# SCH_System.net
KiCad netlist of a schematic drawn in Altium Designer
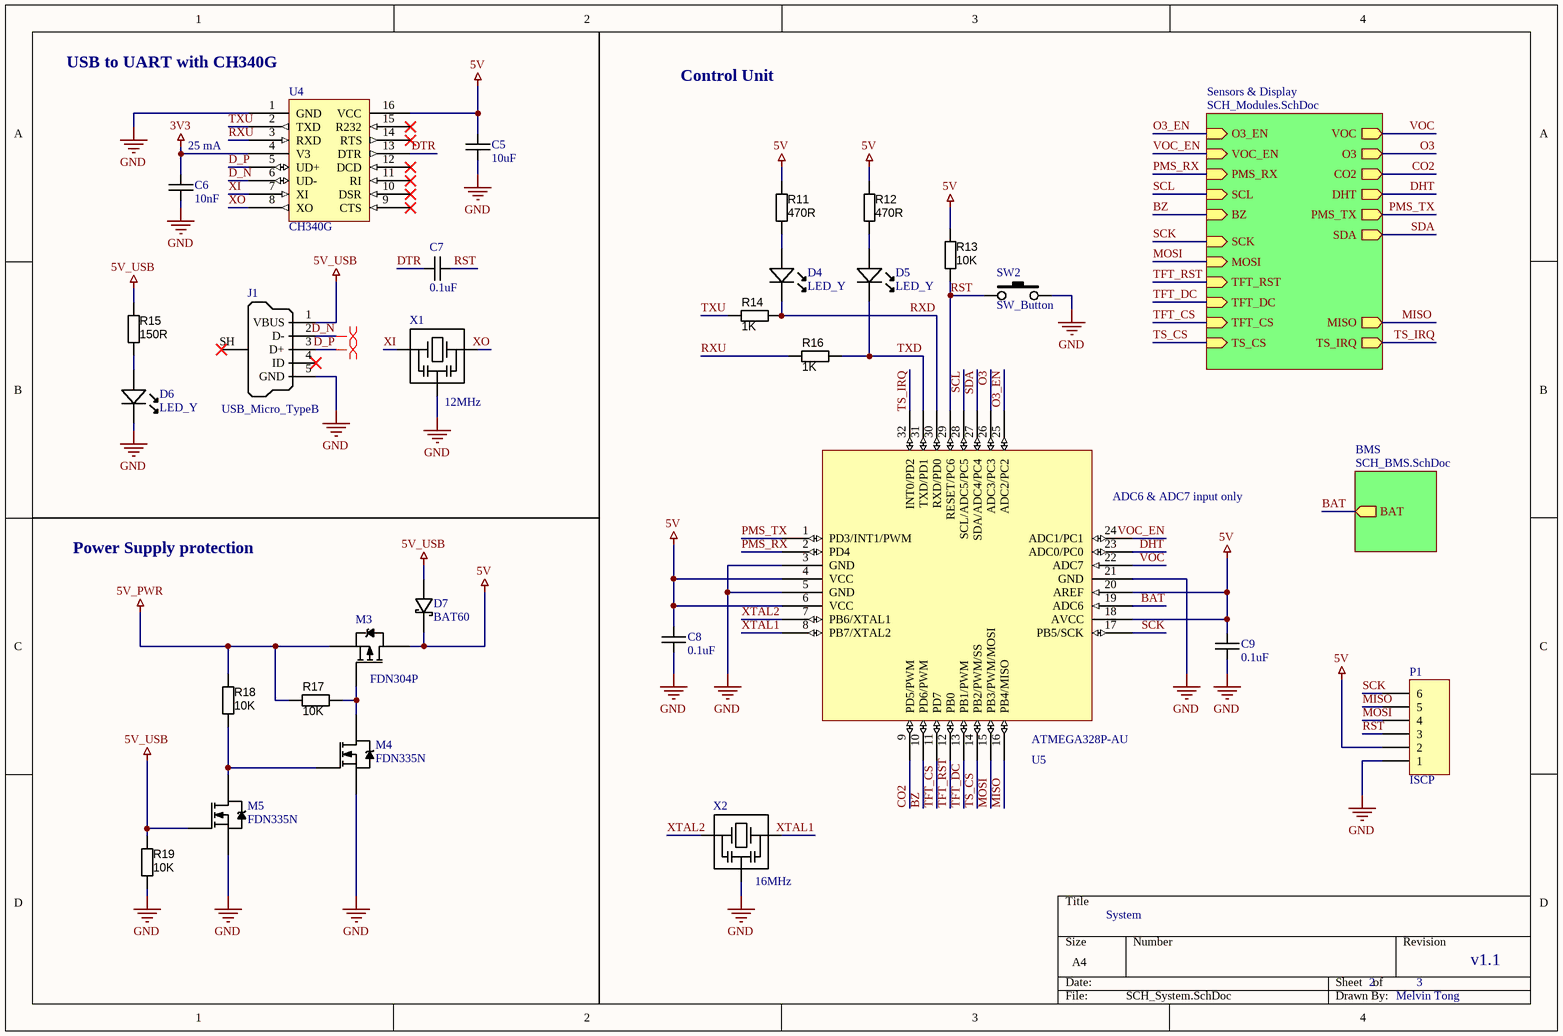
[diagram p0: SCH_System.SchDoc]

(export (version "E")
  (design (tool "Eeschema 10.0.6"))
  (components
    (comp (ref "C5")
      (value "10uF")
      (footprint "CAP_0805")
      (description "SMD 0805")
      (libsource (lib "SchLib_AirMeter") (part "CAP_10uF"))
    )
    (comp (ref "C6")
      (value "10nF")
      (footprint "CAP_0805")
      (description "SMD 0805")
      (libsource (lib "SchLib_AirMeter") (part "CAP_10nF"))
    )
    (comp (ref "C7")
      (value "0.1uF")
      (footprint "CAP_0805")
      (description "SMD 0805")
      (libsource (lib "SchLib_AirMeter") (part "CAP_0.1uF"))
    )
    (comp (ref "C8")
      (value "0.1uF")
      (footprint "CAP_0805")
      (description "SMD 0805")
      (libsource (lib "SchLib_AirMeter") (part "CAP_0.1uF"))
    )
    (comp (ref "C9")
      (value "0.1uF")
      (footprint "CAP_0805")
      (description "SMD 0805")
      (libsource (lib "SchLib_AirMeter") (part "CAP_0.1uF"))
    )
    (comp (ref "D4")
      (value "LED_Y")
      (footprint "LED_0805")
      (description "SMD_0805 2.4V")
      (libsource (lib "SchLib_AirMeter") (part "LED_Y"))
    )
    (comp (ref "D5")
      (value "LED_Y")
      (footprint "LED_0805")
      (description "SMD_0805 2.4V")
      (libsource (lib "SchLib_AirMeter") (part "LED_Y"))
    )
    (comp (ref "D6")
      (value "LED_Y")
      (footprint "LED_0805")
      (description "SMD_0805 2.4V")
      (libsource (lib "SchLib_AirMeter") (part "LED_Y"))
    )
    (comp (ref "D7")
      (value "BAT60")
      (footprint "SOD323")
      (description "Schottky Diode 3A, Vf~0.24V, Vr=10V")
      (libsource (lib "SchLib_AirMeter") (part "BAT60"))
    )
    (comp (ref "J1")
      (value "USB_Micro_TypeB")
      (footprint "USB_Micro_TypeB")
      (libsource (lib "SchLib_AirMeter") (part "USB_Micro_TypeB"))
    )
    (comp (ref "M3")
      (value "FDN304P")
      (footprint "SOT23_213")
      (libsource (lib "SchLib_AirMeter") (part "PMOS"))
    )
    (comp (ref "M4")
      (value "FDN335N")
      (footprint "SOT23_213")
      (libsource (lib "SchLib_AirMeter") (part "NMOS"))
    )
    (comp (ref "M5")
      (value "FDN335N")
      (footprint "SOT23_213")
      (libsource (lib "SchLib_AirMeter") (part "NMOS"))
    )
    (comp (ref "P1")
      (value "ISCP")
      (footprint "HDR1X6")
      (description "Header, 6-Pin")
      (fields (field (name "PUBLISHER") "Altium Limited"))
      (libsource (lib "Miscellaneous Connectors") (part "Header 6"))
    )
    (comp (ref "R11")
      (value "470R")
      (footprint "RESC3216X70N")
      (description "Resistor SMD, 1206")
      (libsource (lib "Schlib_Sword") (part "RES_470R"))
    )
    (comp (ref "R12")
      (value "470R")
      (footprint "RESC3216X70N")
      (description "Resistor SMD, 1206")
      (libsource (lib "") (part "RES_470R_1"))
    )
    (comp (ref "R13")
      (value "10K")
      (footprint "RESC3216X70N")
      (description "Resistor SMD, 1206")
      (libsource (lib "SchLib_AirMeter") (part "RES_10K"))
    )
    (comp (ref "R14")
      (value "1K")
      (footprint "RESC3216X70N")
      (description "Resistor SMD, 1206")
      (libsource (lib "SchLib_AirMeter") (part "RES_1K"))
    )
    (comp (ref "R15")
      (value "150R")
      (footprint "RESC3216X70N")
      (description "Resistor SMD, 1206")
      (libsource (lib "SchLib_AirMeter") (part "RES_150R"))
    )
    (comp (ref "R16")
      (value "1K")
      (footprint "RESC3216X70N")
      (description "Resistor SMD, 1206")
      (libsource (lib "SchLib_AirMeter") (part "RES_1K"))
    )
    (comp (ref "R17")
      (value "10K")
      (footprint "RESC3216X70N")
      (description "Resistor SMD, 1206")
      (libsource (lib "") (part "RES_10K_1"))
    )
    (comp (ref "R18")
      (value "10K")
      (footprint "RESC3216X70N")
      (description "Resistor SMD, 1206")
      (libsource (lib "SchLib_AirMeter") (part "RES_10K"))
    )
    (comp (ref "R19")
      (value "10K")
      (footprint "RESC3216X70N")
      (description "Resistor SMD, 1206")
      (libsource (lib "SchLib_AirMeter") (part "RES_10K"))
    )
    (comp (ref "SW2")
      (value "SW_Button")
      (footprint "Button_4x4x1.5")
      (libsource (lib "SchLib_AirMeter") (part "SW_Button"))
    )
    (comp (ref "U4")
      (value "CH340G")
      (footprint "CH340G")
      (libsource (lib "SchLib_AirMeter") (part "CH340G"))
    )
    (comp (ref "U5")
      (value "ATMEGA328P-AU")
      (footprint "ATMEGA328P-AU")
      (libsource (lib "SchLib_AirMeter") (part "ATMEGA328P-AU"))
    )
    (comp (ref "X1")
      (value "12MHz")
      (footprint "XTAL_3.2x1.6")
      (description "Crystal Oscillator")
      (libsource (lib "SchLib_AirMeter") (part "12MHz"))
    )
    (comp (ref "X2")
      (value "16MHz")
      (footprint "XTAL_3.2x1.6")
      (description "Crystal Oscillator")
      (libsource (lib "SchLib_AirMeter") (part "16MHz"))
    )
  )
  (nets
    (net (code "1") (name "/BAT") (class "Default")
      (node (ref "U5") (pin "19") (pinfunction "ADC6_19") (pintype "input"))
    )
    (net (code "2") (name "/BZ") (class "Default")
      (node (ref "U5") (pin "10") (pinfunction "PD6/PWM_10") (pintype "bidirectional"))
    )
    (net (code "3") (name "/CO2") (class "Default")
      (node (ref "U5") (pin "9") (pinfunction "PD5/PWM_9") (pintype "bidirectional"))
    )
    (net (code "4") (name "/DHT") (class "Default")
      (node (ref "U5") (pin "23") (pinfunction "ADC0/PC0_23") (pintype "bidirectional"))
    )
    (net (code "5") (name "/DTR") (class "Default")
      (node (ref "C7") (pin "1") (pintype "passive"))
      (node (ref "U4") (pin "13") (pinfunction "DTR_13") (pintype "output"))
    )
    (net (code "6") (name "/D_N") (class "Default")
      (node (ref "J1") (pin "2") (pinfunction "D-_2") (pintype "passive"))
      (node (ref "U4") (pin "6") (pinfunction "UD-_6") (pintype "bidirectional"))
    )
    (net (code "7") (name "/D_P") (class "Default")
      (node (ref "J1") (pin "3") (pinfunction "D+_3") (pintype "passive"))
      (node (ref "U4") (pin "5") (pinfunction "UD+_5") (pintype "bidirectional"))
    )
    (net (code "8") (name "/MISO") (class "Default")
      (node (ref "P1") (pin "5") (pinfunction "5_5") (pintype "passive"))
      (node (ref "U5") (pin "16") (pinfunction "PB4/MISO_16") (pintype "bidirectional"))
    )
    (net (code "9") (name "/MOSI") (class "Default")
      (node (ref "P1") (pin "4") (pinfunction "4_4") (pintype "passive"))
      (node (ref "U5") (pin "15") (pinfunction "PB3/PWM/MOSI_15") (pintype "bidirectional"))
    )
    (net (code "10") (name "/O3") (class "Default")
      (node (ref "U5") (pin "26") (pinfunction "ADC3/PC3_26") (pintype "bidirectional"))
    )
    (net (code "11") (name "/O3_EN") (class "Default")
      (node (ref "U5") (pin "25") (pinfunction "ADC2/PC2_25") (pintype "bidirectional"))
    )
    (net (code "12") (name "/PMS_RX") (class "Default")
      (node (ref "U5") (pin "2") (pinfunction "PD4_2") (pintype "bidirectional"))
    )
    (net (code "13") (name "/PMS_TX") (class "Default")
      (node (ref "U5") (pin "1") (pinfunction "PD3/INT1/PWM_1") (pintype "bidirectional"))
    )
    (net (code "14") (name "/RST") (class "Default")
      (node (ref "C7") (pin "2") (pintype "passive"))
      (node (ref "P1") (pin "3") (pinfunction "3_3") (pintype "passive"))
      (node (ref "R13") (pin "2") (pinfunction "2_2") (pintype "passive"))
      (node (ref "SW2") (pin "1") (pintype "passive"))
      (node (ref "U5") (pin "29") (pinfunction "RESET/PC6_29") (pintype "bidirectional"))
    )
    (net (code "15") (name "/RXD") (class "Default")
      (node (ref "D4") (pin "K") (pinfunction "K_K") (pintype "passive"))
      (node (ref "R14") (pin "2") (pinfunction "2_2") (pintype "passive"))
      (node (ref "U5") (pin "30") (pinfunction "RXD/PD0_30") (pintype "bidirectional"))
    )
    (net (code "16") (name "/RXU") (class "Default")
      (node (ref "R16") (pin "1") (pinfunction "1_1") (pintype "passive"))
      (node (ref "U4") (pin "3") (pinfunction "RXD_3") (pintype "input"))
    )
    (net (code "17") (name "/SCK") (class "Default")
      (node (ref "P1") (pin "6") (pinfunction "6_6") (pintype "passive"))
      (node (ref "U5") (pin "17") (pinfunction "PB5/SCK_17") (pintype "bidirectional"))
    )
    (net (code "18") (name "/SCL") (class "Default")
      (node (ref "U5") (pin "28") (pinfunction "SCL/ADC5/PC5_28") (pintype "bidirectional"))
    )
    (net (code "19") (name "/SDA") (class "Default")
      (node (ref "U5") (pin "27") (pinfunction "SDA/ADC4/PC4_27") (pintype "bidirectional"))
    )
    (net (code "20") (name "/TFT_CS") (class "Default")
      (node (ref "U5") (pin "11") (pinfunction "PD7_11") (pintype "bidirectional"))
    )
    (net (code "21") (name "/TFT_DC") (class "Default")
      (node (ref "U5") (pin "13") (pinfunction "PB1/PWM_13") (pintype "bidirectional"))
    )
    (net (code "22") (name "/TFT_RST") (class "Default")
      (node (ref "U5") (pin "12") (pinfunction "PB0_12") (pintype "bidirectional"))
    )
    (net (code "23") (name "/TS_CS") (class "Default")
      (node (ref "U5") (pin "14") (pinfunction "PB2/PWM/SS_14") (pintype "bidirectional"))
    )
    (net (code "24") (name "/TS_IRQ") (class "Default")
      (node (ref "U5") (pin "32") (pinfunction "INT0/PD2_32") (pintype "bidirectional"))
    )
    (net (code "25") (name "/TXD") (class "Default")
      (node (ref "D5") (pin "K") (pinfunction "K_K") (pintype "passive"))
      (node (ref "R16") (pin "2") (pinfunction "2_2") (pintype "passive"))
      (node (ref "U5") (pin "31") (pinfunction "TXD/PD1_31") (pintype "bidirectional"))
    )
    (net (code "26") (name "/TXU") (class "Default")
      (node (ref "R14") (pin "1") (pinfunction "1_1") (pintype "passive"))
      (node (ref "U4") (pin "2") (pinfunction "TXD_2") (pintype "output"))
    )
    (net (code "27") (name "/VOC") (class "Default")
      (node (ref "U5") (pin "22") (pinfunction "ADC7_22") (pintype "input"))
    )
    (net (code "28") (name "/VOC_EN") (class "Default")
      (node (ref "U5") (pin "24") (pinfunction "ADC1/PC1_24") (pintype "bidirectional"))
    )
    (net (code "29") (name "/XI") (class "Default")
      (node (ref "U4") (pin "7") (pinfunction "XI_7") (pintype "input"))
      (node (ref "X1") (pin "1") (pinfunction "IN_1") (pintype "passive"))
    )
    (net (code "30") (name "/XO") (class "Default")
      (node (ref "U4") (pin "8") (pinfunction "XO_8") (pintype "output"))
      (node (ref "X1") (pin "3") (pinfunction "OUT_3") (pintype "passive"))
    )
    (net (code "31") (name "/XTAL1") (class "Default")
      (node (ref "U5") (pin "8") (pinfunction "PB7/XTAL2_8") (pintype "bidirectional"))
      (node (ref "X2") (pin "3") (pinfunction "OUT_3") (pintype "passive"))
    )
    (net (code "32") (name "/XTAL2") (class "Default")
      (node (ref "U5") (pin "7") (pinfunction "PB6/XTAL1_7") (pintype "bidirectional"))
      (node (ref "X2") (pin "1") (pinfunction "IN_1") (pintype "passive"))
    )
    (net (code "33") (name "3V3") (class "Default")
      (node (ref "C6") (pin "1") (pintype "passive"))
      (node (ref "U4") (pin "4") (pinfunction "V3_4") (pintype "power_in"))
    )
    (net (code "34") (name "5V") (class "Default")
      (node (ref "C5") (pin "1") (pintype "passive"))
      (node (ref "C8") (pin "1") (pintype "passive"))
      (node (ref "C9") (pin "1") (pintype "passive"))
      (node (ref "D7") (pin "K") (pinfunction "K_K") (pintype "passive"))
      (node (ref "M3") (pin "3") (pinfunction "D_3") (pintype "passive"))
      (node (ref "P1") (pin "2") (pinfunction "2_2") (pintype "passive"))
      (node (ref "R11") (pin "2") (pinfunction "2_2") (pintype "passive"))
      (node (ref "R12") (pin "1") (pinfunction "1_1") (pintype "passive"))
      (node (ref "R13") (pin "1") (pinfunction "1_1") (pintype "passive"))
      (node (ref "U4") (pin "16") (pinfunction "VCC_16") (pintype "power_in"))
      (node (ref "U5") (pin "18") (pinfunction "AVCC_18") (pintype "power_in"))
      (node (ref "U5") (pin "20") (pinfunction "AREF_20") (pintype "input"))
      (node (ref "U5") (pin "4") (pinfunction "VCC_4") (pintype "power_in"))
      (node (ref "U5") (pin "6") (pinfunction "VCC_6") (pintype "power_in"))
    )
    (net (code "35") (name "5V_PWR") (class "Default")
      (node (ref "M3") (pin "2") (pinfunction "S_2") (pintype "passive"))
      (node (ref "R17") (pin "1") (pinfunction "1_1") (pintype "passive"))
      (node (ref "R18") (pin "1") (pinfunction "1_1") (pintype "passive"))
    )
    (net (code "36") (name "5V_USB") (class "Default")
      (node (ref "D7") (pin "A") (pinfunction "A_A") (pintype "passive"))
      (node (ref "J1") (pin "1") (pinfunction "VBUS_1") (pintype "passive"))
      (node (ref "M5") (pin "1") (pinfunction "G_1") (pintype "passive"))
      (node (ref "R15") (pin "1") (pinfunction "1_1") (pintype "passive"))
      (node (ref "R19") (pin "1") (pinfunction "1_1") (pintype "passive"))
    )
    (net (code "37") (name "GND") (class "Default")
      (node (ref "C5") (pin "2") (pintype "passive"))
      (node (ref "C6") (pin "2") (pintype "passive"))
      (node (ref "C8") (pin "2") (pintype "passive"))
      (node (ref "C9") (pin "2") (pintype "passive"))
      (node (ref "D6") (pin "K") (pinfunction "K_K") (pintype "passive"))
      (node (ref "J1") (pin "5") (pinfunction "GND_5") (pintype "passive"))
      (node (ref "M4") (pin "2") (pinfunction "S_2") (pintype "passive"))
      (node (ref "M5") (pin "2") (pinfunction "S_2") (pintype "passive"))
      (node (ref "P1") (pin "1") (pinfunction "1_1") (pintype "passive"))
      (node (ref "R19") (pin "2") (pinfunction "2_2") (pintype "passive"))
      (node (ref "SW2") (pin "2") (pintype "passive"))
      (node (ref "U4") (pin "1") (pinfunction "GND_1") (pintype "power_in"))
      (node (ref "U5") (pin "21") (pinfunction "GND_21") (pintype "power_in"))
      (node (ref "U5") (pin "3") (pinfunction "GND_3") (pintype "power_in"))
      (node (ref "U5") (pin "5") (pinfunction "GND_5") (pintype "power_in"))
      (node (ref "X1") (pin "2") (pinfunction "GND_2") (pintype "passive"))
      (node (ref "X2") (pin "2") (pinfunction "GND_2") (pintype "passive"))
    )
    (net (code "38") (name "Net-(D4-PadA)") (class "Default")
      (node (ref "D4") (pin "A") (pinfunction "A_A") (pintype "passive"))
      (node (ref "R11") (pin "1") (pinfunction "1_1") (pintype "passive"))
    )
    (net (code "39") (name "Net-(D5-PadA)") (class "Default")
      (node (ref "D5") (pin "A") (pinfunction "A_A") (pintype "passive"))
      (node (ref "R12") (pin "2") (pinfunction "2_2") (pintype "passive"))
    )
    (net (code "40") (name "Net-(D6-PadA)") (class "Default")
      (node (ref "D6") (pin "A") (pinfunction "A_A") (pintype "passive"))
      (node (ref "R15") (pin "2") (pinfunction "2_2") (pintype "passive"))
    )
    (net (code "41") (name "Net-(M3-G)") (class "Default")
      (node (ref "M3") (pin "1") (pinfunction "G_1") (pintype "passive"))
      (node (ref "M4") (pin "3") (pinfunction "D_3") (pintype "passive"))
      (node (ref "R17") (pin "2") (pinfunction "2_2") (pintype "passive"))
    )
    (net (code "42") (name "Net-(M4-G)") (class "Default")
      (node (ref "M4") (pin "1") (pinfunction "G_1") (pintype "passive"))
      (node (ref "M5") (pin "3") (pinfunction "D_3") (pintype "passive"))
      (node (ref "R18") (pin "2") (pinfunction "2_2") (pintype "passive"))
    )
    (net (code "43") (name "unconnected-(J1-ID-Pad4)") (class "Default")
      (node (ref "J1") (pin "4") (pinfunction "ID_4") (pintype "passive+no_connect"))
    )
    (net (code "44") (name "unconnected-(J1-Shell-PadSH)") (class "Default")
      (node (ref "J1") (pin "SH") (pinfunction "Shell_SH") (pintype "passive+no_connect"))
    )
    (net (code "45") (name "unconnected-(U4-CTS-Pad9)") (class "Default")
      (node (ref "U4") (pin "9") (pinfunction "CTS_9") (pintype "input+no_connect"))
    )
    (net (code "46") (name "unconnected-(U4-DCD-Pad12)") (class "Default")
      (node (ref "U4") (pin "12") (pinfunction "DCD_12") (pintype "input+no_connect"))
    )
    (net (code "47") (name "unconnected-(U4-DSR-Pad10)") (class "Default")
      (node (ref "U4") (pin "10") (pinfunction "DSR_10") (pintype "input+no_connect"))
    )
    (net (code "48") (name "unconnected-(U4-R232-Pad15)") (class "Default")
      (node (ref "U4") (pin "15") (pinfunction "R232_15") (pintype "input+no_connect"))
    )
    (net (code "49") (name "unconnected-(U4-RI-Pad11)") (class "Default")
      (node (ref "U4") (pin "11") (pinfunction "RI_11") (pintype "input+no_connect"))
    )
    (net (code "50") (name "unconnected-(U4-RTS-Pad14)") (class "Default")
      (node (ref "U4") (pin "14") (pinfunction "RTS_14") (pintype "output+no_connect"))
    )
  )
)
